# mosaico-dock-schematic.net
KiCad netlist of a schematic drawn in EasyEDA
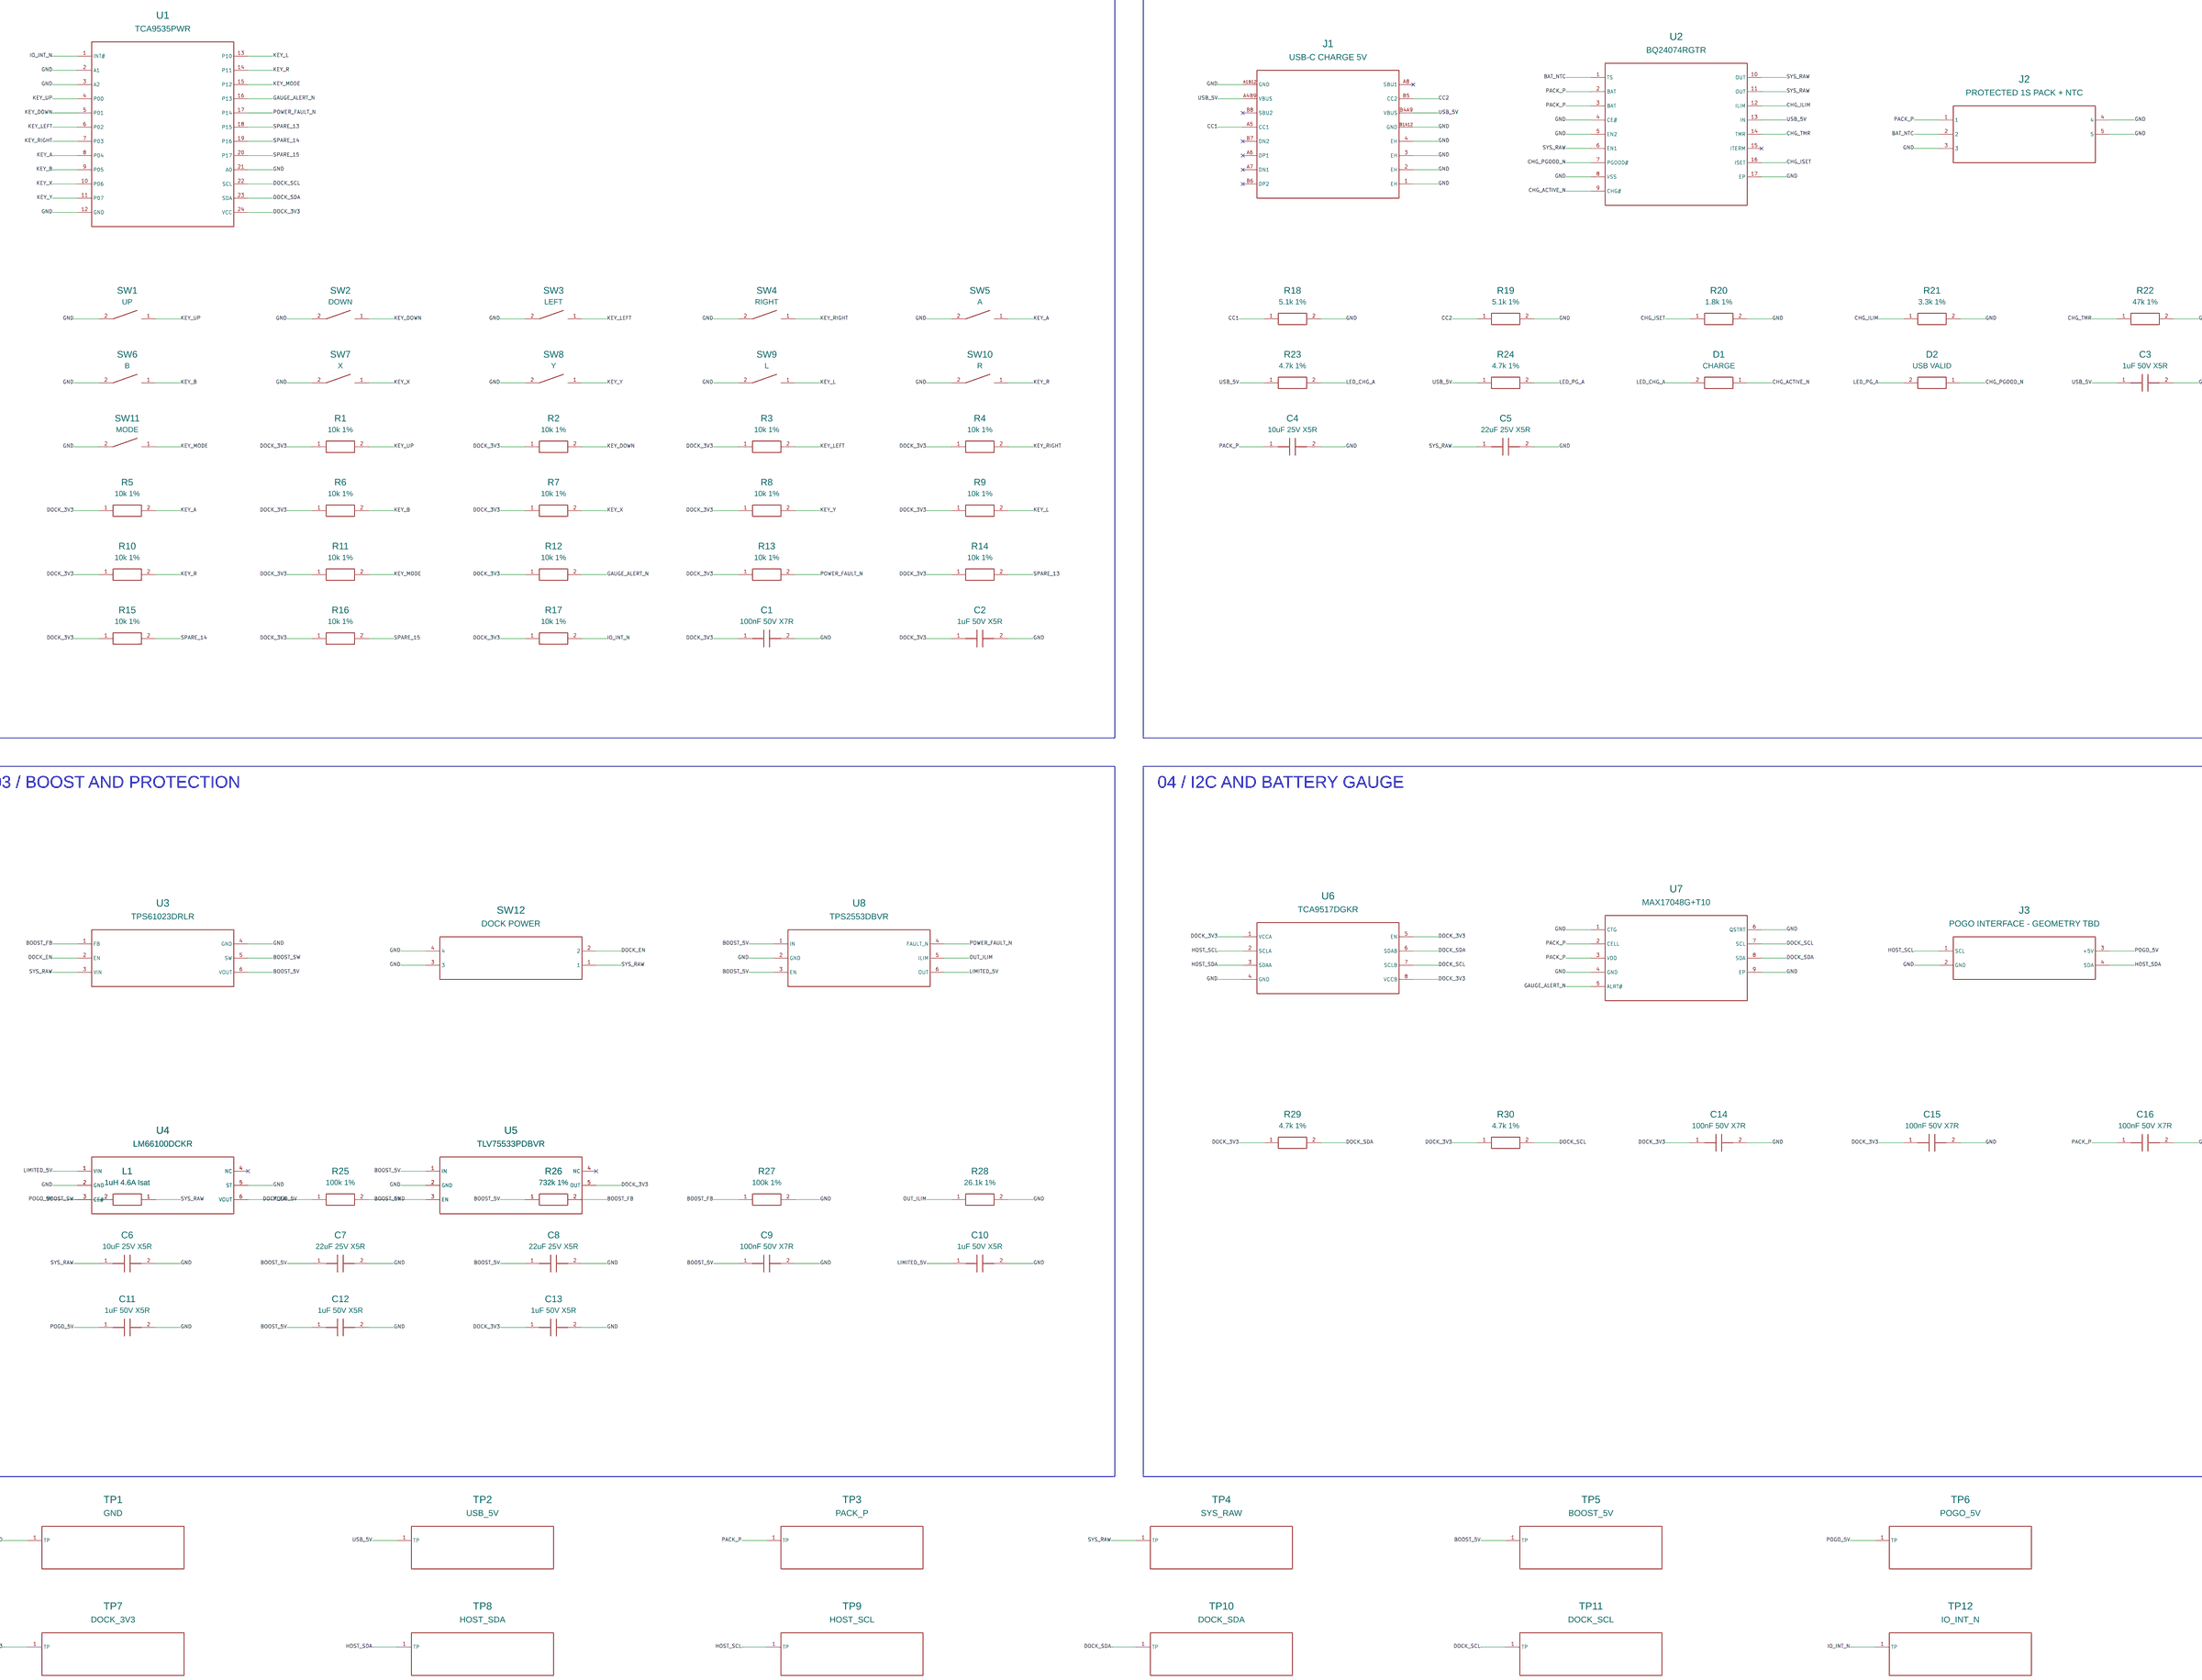
[diagram p0: schematic sheet]

(export (version "E")
  (design (tool "Eeschema 10.0.6"))
  (components
    (comp (ref "C1")
      (value "100nF 50V X7R")
      (fields
        (field (name "Manufacturer Part") "CL10B104KB8NNNC")
        (field (name "Manufacturer") "SAMSUNG(三星)")
      )
      (libsource (lib "") (part "100nF 50V X7R"))
    )
    (comp (ref "C2")
      (value "1uF 50V X5R")
      (fields
        (field (name "Manufacturer Part") "CL10A105KB8NNNC")
        (field (name "Manufacturer") "SAMSUNG(三星)")
      )
      (libsource (lib "") (part "1uF 50V X5R"))
    )
    (comp (ref "C3")
      (value "1uF 50V X5R")
      (fields
        (field (name "Manufacturer Part") "CL10A105KB8NNNC")
        (field (name "Manufacturer") "SAMSUNG(三星)")
      )
      (libsource (lib "") (part "1uF 50V X5R"))
    )
    (comp (ref "C4")
      (value "10uF 25V X5R")
      (fields
        (field (name "Manufacturer Part") "CL10A106MA8NRNC")
        (field (name "Manufacturer") "SAMSUNG(三星)")
      )
      (libsource (lib "") (part "10uF 25V X5R"))
    )
    (comp (ref "C5")
      (value "22uF 25V X5R")
      (fields
        (field (name "Manufacturer Part") "CL21A226MAQNNNE")
        (field (name "Manufacturer") "SAMSUNG(三星)")
      )
      (libsource (lib "") (part "22uF 25V X5R"))
    )
    (comp (ref "C6")
      (value "10uF 25V X5R")
      (fields
        (field (name "Manufacturer Part") "CL10A106MA8NRNC")
        (field (name "Manufacturer") "SAMSUNG(三星)")
      )
      (libsource (lib "") (part "10uF 25V X5R"))
    )
    (comp (ref "C7")
      (value "22uF 25V X5R")
      (fields
        (field (name "Manufacturer Part") "CL21A226MAQNNNE")
        (field (name "Manufacturer") "SAMSUNG(三星)")
      )
      (libsource (lib "") (part "22uF 25V X5R"))
    )
    (comp (ref "C8")
      (value "22uF 25V X5R")
      (fields
        (field (name "Manufacturer Part") "CL21A226MAQNNNE")
        (field (name "Manufacturer") "SAMSUNG(三星)")
      )
      (libsource (lib "") (part "22uF 25V X5R"))
    )
    (comp (ref "C9")
      (value "100nF 50V X7R")
      (fields
        (field (name "Manufacturer Part") "CL10B104KB8NNNC")
        (field (name "Manufacturer") "SAMSUNG(三星)")
      )
      (libsource (lib "") (part "100nF 50V X7R"))
    )
    (comp (ref "C10")
      (value "1uF 50V X5R")
      (fields
        (field (name "Manufacturer Part") "CL10A105KB8NNNC")
        (field (name "Manufacturer") "SAMSUNG(三星)")
      )
      (libsource (lib "") (part "1uF 50V X5R"))
    )
    (comp (ref "C11")
      (value "1uF 50V X5R")
      (fields
        (field (name "Manufacturer Part") "CL10A105KB8NNNC")
        (field (name "Manufacturer") "SAMSUNG(三星)")
      )
      (libsource (lib "") (part "1uF 50V X5R"))
    )
    (comp (ref "C12")
      (value "1uF 50V X5R")
      (fields
        (field (name "Manufacturer Part") "CL10A105KB8NNNC")
        (field (name "Manufacturer") "SAMSUNG(三星)")
      )
      (libsource (lib "") (part "1uF 50V X5R"))
    )
    (comp (ref "C13")
      (value "1uF 50V X5R")
      (fields
        (field (name "Manufacturer Part") "CL10A105KB8NNNC")
        (field (name "Manufacturer") "SAMSUNG(三星)")
      )
      (libsource (lib "") (part "1uF 50V X5R"))
    )
    (comp (ref "C14")
      (value "100nF 50V X7R")
      (fields
        (field (name "Manufacturer Part") "CL10B104KB8NNNC")
        (field (name "Manufacturer") "SAMSUNG(三星)")
      )
      (libsource (lib "") (part "100nF 50V X7R"))
    )
    (comp (ref "C15")
      (value "100nF 50V X7R")
      (fields
        (field (name "Manufacturer Part") "CL10B104KB8NNNC")
        (field (name "Manufacturer") "SAMSUNG(三星)")
      )
      (libsource (lib "") (part "100nF 50V X7R"))
    )
    (comp (ref "C16")
      (value "100nF 50V X7R")
      (fields
        (field (name "Manufacturer Part") "CL10B104KB8NNNC")
        (field (name "Manufacturer") "SAMSUNG(三星)")
      )
      (libsource (lib "") (part "100nF 50V X7R"))
    )
    (comp (ref "D1")
      (value "CHARGE")
      (fields (field (name "Manufacturer Part") "KT-0805黄灯") (field (name "Manufacturer") "KENTO"))
      (libsource (lib "") (part "CHARGE"))
    )
    (comp (ref "D2")
      (value "USB VALID")
      (fields (field (name "Manufacturer Part") "KT-0805黄灯") (field (name "Manufacturer") "KENTO"))
      (libsource (lib "") (part "USB VALID"))
    )
    (comp (ref "J1")
      (value "USB-C CHARGE 5V")
      (fields (field (name "Manufacturer Part") "TYPE-C-31-M-12") (field (name "Manufacturer") "韩国韩荣"))
      (libsource (lib "") (part "USB-C CHARGE 5V"))
    )
    (comp (ref "J2")
      (value "PROTECTED 1S PACK + NTC")
      (fields (field (name "Manufacturer Part") "B3B-PH-SM4-TB(LF)(SN)") (field (name "Manufacturer") "JST"))
      (libsource (lib "") (part "PROTECTED 1S PACK + NTC"))
    )
    (comp (ref "J3")
      (value "POGO INTERFACE - GEOMETRY TBD")
      (libsource (lib "") (part "POGO INTERFACE - GEOMETRY TBD"))
    )
    (comp (ref "L1")
      (value "1uH 4.6A Isat")
      (fields
        (field (name "Manufacturer Part") "FTC201610S1R0MBCA")
        (field (name "Manufacturer") "cjiang(长江微电)")
      )
      (libsource (lib "") (part "1uH 4.6A Isat"))
    )
    (comp (ref "R1")
      (value "10k 1%")
      (fields
        (field (name "Manufacturer Part") "0603WAF1002T5E")
        (field (name "Manufacturer") "UNI-ROYAL(厚声)")
      )
      (libsource (lib "") (part "10k 1%"))
    )
    (comp (ref "R2")
      (value "10k 1%")
      (fields
        (field (name "Manufacturer Part") "0603WAF1002T5E")
        (field (name "Manufacturer") "UNI-ROYAL(厚声)")
      )
      (libsource (lib "") (part "10k 1%"))
    )
    (comp (ref "R3")
      (value "10k 1%")
      (fields
        (field (name "Manufacturer Part") "0603WAF1002T5E")
        (field (name "Manufacturer") "UNI-ROYAL(厚声)")
      )
      (libsource (lib "") (part "10k 1%"))
    )
    (comp (ref "R4")
      (value "10k 1%")
      (fields
        (field (name "Manufacturer Part") "0603WAF1002T5E")
        (field (name "Manufacturer") "UNI-ROYAL(厚声)")
      )
      (libsource (lib "") (part "10k 1%"))
    )
    (comp (ref "R5")
      (value "10k 1%")
      (fields
        (field (name "Manufacturer Part") "0603WAF1002T5E")
        (field (name "Manufacturer") "UNI-ROYAL(厚声)")
      )
      (libsource (lib "") (part "10k 1%"))
    )
    (comp (ref "R6")
      (value "10k 1%")
      (fields
        (field (name "Manufacturer Part") "0603WAF1002T5E")
        (field (name "Manufacturer") "UNI-ROYAL(厚声)")
      )
      (libsource (lib "") (part "10k 1%"))
    )
    (comp (ref "R7")
      (value "10k 1%")
      (fields
        (field (name "Manufacturer Part") "0603WAF1002T5E")
        (field (name "Manufacturer") "UNI-ROYAL(厚声)")
      )
      (libsource (lib "") (part "10k 1%"))
    )
    (comp (ref "R8")
      (value "10k 1%")
      (fields
        (field (name "Manufacturer Part") "0603WAF1002T5E")
        (field (name "Manufacturer") "UNI-ROYAL(厚声)")
      )
      (libsource (lib "") (part "10k 1%"))
    )
    (comp (ref "R9")
      (value "10k 1%")
      (fields
        (field (name "Manufacturer Part") "0603WAF1002T5E")
        (field (name "Manufacturer") "UNI-ROYAL(厚声)")
      )
      (libsource (lib "") (part "10k 1%"))
    )
    (comp (ref "R10")
      (value "10k 1%")
      (fields
        (field (name "Manufacturer Part") "0603WAF1002T5E")
        (field (name "Manufacturer") "UNI-ROYAL(厚声)")
      )
      (libsource (lib "") (part "10k 1%"))
    )
    (comp (ref "R11")
      (value "10k 1%")
      (fields
        (field (name "Manufacturer Part") "0603WAF1002T5E")
        (field (name "Manufacturer") "UNI-ROYAL(厚声)")
      )
      (libsource (lib "") (part "10k 1%"))
    )
    (comp (ref "R12")
      (value "10k 1%")
      (fields
        (field (name "Manufacturer Part") "0603WAF1002T5E")
        (field (name "Manufacturer") "UNI-ROYAL(厚声)")
      )
      (libsource (lib "") (part "10k 1%"))
    )
    (comp (ref "R13")
      (value "10k 1%")
      (fields
        (field (name "Manufacturer Part") "0603WAF1002T5E")
        (field (name "Manufacturer") "UNI-ROYAL(厚声)")
      )
      (libsource (lib "") (part "10k 1%"))
    )
    (comp (ref "R14")
      (value "10k 1%")
      (fields
        (field (name "Manufacturer Part") "0603WAF1002T5E")
        (field (name "Manufacturer") "UNI-ROYAL(厚声)")
      )
      (libsource (lib "") (part "10k 1%"))
    )
    (comp (ref "R15")
      (value "10k 1%")
      (fields
        (field (name "Manufacturer Part") "0603WAF1002T5E")
        (field (name "Manufacturer") "UNI-ROYAL(厚声)")
      )
      (libsource (lib "") (part "10k 1%"))
    )
    (comp (ref "R16")
      (value "10k 1%")
      (fields
        (field (name "Manufacturer Part") "0603WAF1002T5E")
        (field (name "Manufacturer") "UNI-ROYAL(厚声)")
      )
      (libsource (lib "") (part "10k 1%"))
    )
    (comp (ref "R17")
      (value "10k 1%")
      (fields
        (field (name "Manufacturer Part") "0603WAF1002T5E")
        (field (name "Manufacturer") "UNI-ROYAL(厚声)")
      )
      (libsource (lib "") (part "10k 1%"))
    )
    (comp (ref "R18")
      (value "5.1k 1%")
      (fields
        (field (name "Manufacturer Part") "0603WAF5101T5E")
        (field (name "Manufacturer") "UNI-ROYAL(厚声)")
      )
      (libsource (lib "") (part "5.1k 1%"))
    )
    (comp (ref "R19")
      (value "5.1k 1%")
      (fields
        (field (name "Manufacturer Part") "0603WAF5101T5E")
        (field (name "Manufacturer") "UNI-ROYAL(厚声)")
      )
      (libsource (lib "") (part "5.1k 1%"))
    )
    (comp (ref "R20")
      (value "1.8k 1%")
      (fields
        (field (name "Manufacturer Part") "0603WAF1801T5E")
        (field (name "Manufacturer") "UNI-ROYAL(厚声)")
      )
      (libsource (lib "") (part "1.8k 1%"))
    )
    (comp (ref "R21")
      (value "3.3k 1%")
      (fields
        (field (name "Manufacturer Part") "0603WAF3301T5E")
        (field (name "Manufacturer") "UNI-ROYAL(厚声)")
      )
      (libsource (lib "") (part "3.3k 1%"))
    )
    (comp (ref "R22")
      (value "47k 1%")
      (fields
        (field (name "Manufacturer Part") "0603WAF4702T5E")
        (field (name "Manufacturer") "UNI-ROYAL(厚声)")
      )
      (libsource (lib "") (part "47k 1%"))
    )
    (comp (ref "R23")
      (value "4.7k 1%")
      (fields
        (field (name "Manufacturer Part") "0603WAF4701T5E")
        (field (name "Manufacturer") "UNI-ROYAL(厚声)")
      )
      (libsource (lib "") (part "4.7k 1%"))
    )
    (comp (ref "R24")
      (value "4.7k 1%")
      (fields
        (field (name "Manufacturer Part") "0603WAF4701T5E")
        (field (name "Manufacturer") "UNI-ROYAL(厚声)")
      )
      (libsource (lib "") (part "4.7k 1%"))
    )
    (comp (ref "R25")
      (value "100k 1%")
      (fields
        (field (name "Manufacturer Part") "0603WAF1003T5E")
        (field (name "Manufacturer") "UNI-ROYAL(厚声)")
      )
      (libsource (lib "") (part "100k 1%"))
    )
    (comp (ref "R26") (value "732k 1%") (libsource (lib "") (part "732k 1%")))
    (comp (ref "R27")
      (value "100k 1%")
      (fields
        (field (name "Manufacturer Part") "0603WAF1003T5E")
        (field (name "Manufacturer") "UNI-ROYAL(厚声)")
      )
      (libsource (lib "") (part "100k 1%"))
    )
    (comp (ref "R28") (value "26.1k 1%") (libsource (lib "") (part "26.1k 1%")))
    (comp (ref "R29")
      (value "4.7k 1%")
      (fields
        (field (name "Manufacturer Part") "0603WAF4701T5E")
        (field (name "Manufacturer") "UNI-ROYAL(厚声)")
      )
      (libsource (lib "") (part "4.7k 1%"))
    )
    (comp (ref "R30")
      (value "4.7k 1%")
      (fields
        (field (name "Manufacturer Part") "0603WAF4701T5E")
        (field (name "Manufacturer") "UNI-ROYAL(厚声)")
      )
      (libsource (lib "") (part "4.7k 1%"))
    )
    (comp (ref "SW1")
      (value "UP")
      (fields (field (name "Manufacturer Part") "TS-1088-AR02016") (field (name "Manufacturer") "XUNPU(讯普)"))
      (libsource (lib "") (part "UP"))
    )
    (comp (ref "SW2")
      (value "DOWN")
      (fields (field (name "Manufacturer Part") "TS-1088-AR02016") (field (name "Manufacturer") "XUNPU(讯普)"))
      (libsource (lib "") (part "DOWN"))
    )
    (comp (ref "SW3")
      (value "LEFT")
      (fields (field (name "Manufacturer Part") "TS-1088-AR02016") (field (name "Manufacturer") "XUNPU(讯普)"))
      (libsource (lib "") (part "LEFT"))
    )
    (comp (ref "SW4")
      (value "RIGHT")
      (fields (field (name "Manufacturer Part") "TS-1088-AR02016") (field (name "Manufacturer") "XUNPU(讯普)"))
      (libsource (lib "") (part "RIGHT"))
    )
    (comp (ref "SW5")
      (value "A")
      (fields (field (name "Manufacturer Part") "TS-1088-AR02016") (field (name "Manufacturer") "XUNPU(讯普)"))
      (libsource (lib "") (part "A"))
    )
    (comp (ref "SW6")
      (value "B")
      (fields (field (name "Manufacturer Part") "TS-1088-AR02016") (field (name "Manufacturer") "XUNPU(讯普)"))
      (libsource (lib "") (part "B"))
    )
    (comp (ref "SW7")
      (value "X")
      (fields (field (name "Manufacturer Part") "TS-1088-AR02016") (field (name "Manufacturer") "XUNPU(讯普)"))
      (libsource (lib "") (part "X"))
    )
    (comp (ref "SW8")
      (value "Y")
      (fields (field (name "Manufacturer Part") "TS-1088-AR02016") (field (name "Manufacturer") "XUNPU(讯普)"))
      (libsource (lib "") (part "Y"))
    )
    (comp (ref "SW9")
      (value "L")
      (fields (field (name "Manufacturer Part") "TS-1088-AR02016") (field (name "Manufacturer") "XUNPU(讯普)"))
      (libsource (lib "") (part "L"))
    )
    (comp (ref "SW10")
      (value "R")
      (fields (field (name "Manufacturer Part") "TS-1088-AR02016") (field (name "Manufacturer") "XUNPU(讯普)"))
      (libsource (lib "") (part "R"))
    )
    (comp (ref "SW11")
      (value "MODE")
      (fields (field (name "Manufacturer Part") "TS-1088-AR02016") (field (name "Manufacturer") "XUNPU(讯普)"))
      (libsource (lib "") (part "MODE"))
    )
    (comp (ref "SW12")
      (value "DOCK POWER")
      (fields (field (name "Manufacturer Part") "MSK12C02") (field (name "Manufacturer") "SHOU HAN(首韩)"))
      (libsource (lib "") (part "DOCK POWER"))
    )
    (comp (ref "TP1") (value "GND") (libsource (lib "") (part "GND")))
    (comp (ref "TP2") (value "USB_5V") (libsource (lib "") (part "USB_5V")))
    (comp (ref "TP3") (value "PACK_P") (libsource (lib "") (part "PACK_P")))
    (comp (ref "TP4") (value "SYS_RAW") (libsource (lib "") (part "SYS_RAW")))
    (comp (ref "TP5") (value "BOOST_5V") (libsource (lib "") (part "BOOST_5V")))
    (comp (ref "TP6") (value "POGO_5V") (libsource (lib "") (part "POGO_5V")))
    (comp (ref "TP7") (value "DOCK_3V3") (libsource (lib "") (part "DOCK_3V3")))
    (comp (ref "TP8") (value "HOST_SDA") (libsource (lib "") (part "HOST_SDA")))
    (comp (ref "TP9") (value "HOST_SCL") (libsource (lib "") (part "HOST_SCL")))
    (comp (ref "TP10") (value "DOCK_SDA") (libsource (lib "") (part "DOCK_SDA")))
    (comp (ref "TP11") (value "DOCK_SCL") (libsource (lib "") (part "DOCK_SCL")))
    (comp (ref "TP12") (value "IO_INT_N") (libsource (lib "") (part "IO_INT_N")))
    (comp (ref "U1")
      (value "TCA9535PWR")
      (fields (field (name "Manufacturer") "TI(德州仪器)"))
      (libsource (lib "") (part "TCA9535PWR"))
    )
    (comp (ref "U2")
      (value "BQ24074RGTR")
      (fields (field (name "Manufacturer") "TI(德州仪器)"))
      (libsource (lib "") (part "BQ24074RGTR"))
    )
    (comp (ref "U3")
      (value "TPS61023DRLR")
      (fields (field (name "Manufacturer") "TI(德州仪器)"))
      (libsource (lib "") (part "TPS61023DRLR"))
    )
    (comp (ref "U4")
      (value "LM66100DCKR")
      (fields (field (name "Manufacturer") "TI(德州仪器)"))
      (libsource (lib "") (part "LM66100DCKR"))
    )
    (comp (ref "U5")
      (value "TLV75533PDBVR")
      (fields (field (name "Manufacturer") "TI(德州仪器)"))
      (libsource (lib "") (part "TLV75533PDBVR"))
    )
    (comp (ref "U6")
      (value "TCA9517DGKR")
      (fields (field (name "Manufacturer") "TI(德州仪器)"))
      (libsource (lib "") (part "TCA9517DGKR"))
    )
    (comp (ref "U7")
      (value "MAX17048G+T10")
      (fields (field (name "Manufacturer") "ADI(亚德诺)/MAXIM(美信)"))
      (libsource (lib "") (part "MAX17048G+T10"))
    )
    (comp (ref "U8")
      (value "TPS2553DBVR")
      (fields (field (name "Manufacturer") "TI(德州仪器)"))
      (libsource (lib "") (part "TPS2553DBVR"))
    )
  )
  (nets
    (net (code "1") (name "/BAT_NTC") (class "Default")
      (node (ref "J2") (pin "2") (pinfunction "2_2") (pintype "unspecified"))
      (node (ref "U2") (pin "1") (pinfunction "TS_1") (pintype "unspecified"))
    )
    (net (code "2") (name "/BOOST_5V") (class "Default")
      (node (ref "C12") (pin "1") (pintype "unspecified"))
      (node (ref "C7") (pin "1") (pintype "unspecified"))
      (node (ref "C8") (pin "1") (pintype "unspecified"))
      (node (ref "C9") (pin "1") (pintype "unspecified"))
      (node (ref "R26") (pin "1") (pintype "unspecified"))
      (node (ref "TP5") (pin "1") (pinfunction "TP_1") (pintype "unspecified"))
      (node (ref "U3") (pin "6") (pinfunction "VOUT_6") (pintype "unspecified"))
      (node (ref "U5") (pin "1") (pinfunction "IN_1") (pintype "unspecified"))
      (node (ref "U5") (pin "3") (pinfunction "EN_3") (pintype "unspecified"))
      (node (ref "U8") (pin "1") (pinfunction "IN_1") (pintype "unspecified"))
      (node (ref "U8") (pin "3") (pinfunction "EN_3") (pintype "unspecified"))
    )
    (net (code "3") (name "/BOOST_FB") (class "Default")
      (node (ref "R26") (pin "2") (pintype "unspecified"))
      (node (ref "R27") (pin "1") (pintype "unspecified"))
      (node (ref "U3") (pin "1") (pinfunction "FB_1") (pintype "unspecified"))
    )
    (net (code "4") (name "/BOOST_SW") (class "Default")
      (node (ref "C11") (pin "1") (pintype "unspecified"))
      (node (ref "J3") (pin "3") (pinfunction "+5V_3") (pintype "unspecified"))
      (node (ref "L1") (pin "2") (pintype "unspecified"))
      (node (ref "TP6") (pin "1") (pinfunction "TP_1") (pintype "unspecified"))
      (node (ref "U3") (pin "5") (pinfunction "SW_5") (pintype "unspecified"))
      (node (ref "U4") (pin "3") (pinfunction "CE#_3") (pintype "unspecified"))
      (node (ref "U4") (pin "6") (pinfunction "VOUT_6") (pintype "unspecified"))
    )
    (net (code "5") (name "/CC1") (class "Default")
      (node (ref "J1") (pin "A5") (pinfunction "CC1_A5") (pintype "unspecified"))
      (node (ref "R18") (pin "1") (pintype "unspecified"))
    )
    (net (code "6") (name "/CC2") (class "Default")
      (node (ref "J1") (pin "B5") (pinfunction "CC2_B5") (pintype "unspecified"))
      (node (ref "R19") (pin "1") (pintype "unspecified"))
    )
    (net (code "7") (name "/CHG_ACTIVE_N") (class "Default")
      (node (ref "D1") (pin "1") (pintype "unspecified"))
      (node (ref "U2") (pin "9") (pinfunction "CHG#_9") (pintype "unspecified"))
    )
    (net (code "8") (name "/CHG_ILIM") (class "Default")
      (node (ref "R21") (pin "1") (pintype "unspecified"))
      (node (ref "U2") (pin "12") (pinfunction "ILIM_12") (pintype "unspecified"))
    )
    (net (code "9") (name "/CHG_ISET") (class "Default")
      (node (ref "R20") (pin "1") (pintype "unspecified"))
      (node (ref "U2") (pin "16") (pinfunction "ISET_16") (pintype "unspecified"))
    )
    (net (code "10") (name "/CHG_PGOOD_N") (class "Default")
      (node (ref "D2") (pin "1") (pintype "unspecified"))
      (node (ref "U2") (pin "7") (pinfunction "PGOOD#_7") (pintype "unspecified"))
    )
    (net (code "11") (name "/CHG_TMR") (class "Default")
      (node (ref "R22") (pin "1") (pintype "unspecified"))
      (node (ref "U2") (pin "14") (pinfunction "TMR_14") (pintype "unspecified"))
    )
    (net (code "12") (name "/DOCK_3V3") (class "Default")
      (node (ref "C1") (pin "1") (pintype "unspecified"))
      (node (ref "C13") (pin "1") (pintype "unspecified"))
      (node (ref "C14") (pin "1") (pintype "unspecified"))
      (node (ref "C15") (pin "1") (pintype "unspecified"))
      (node (ref "C2") (pin "1") (pintype "unspecified"))
      (node (ref "R1") (pin "1") (pintype "unspecified"))
      (node (ref "R10") (pin "1") (pintype "unspecified"))
      (node (ref "R11") (pin "1") (pintype "unspecified"))
      (node (ref "R12") (pin "1") (pintype "unspecified"))
      (node (ref "R13") (pin "1") (pintype "unspecified"))
      (node (ref "R14") (pin "1") (pintype "unspecified"))
      (node (ref "R15") (pin "1") (pintype "unspecified"))
      (node (ref "R16") (pin "1") (pintype "unspecified"))
      (node (ref "R17") (pin "1") (pintype "unspecified"))
      (node (ref "R2") (pin "1") (pintype "unspecified"))
      (node (ref "R29") (pin "1") (pintype "unspecified"))
      (node (ref "R3") (pin "1") (pintype "unspecified"))
      (node (ref "R30") (pin "1") (pintype "unspecified"))
      (node (ref "R4") (pin "1") (pintype "unspecified"))
      (node (ref "R5") (pin "1") (pintype "unspecified"))
      (node (ref "R6") (pin "1") (pintype "unspecified"))
      (node (ref "R7") (pin "1") (pintype "unspecified"))
      (node (ref "R8") (pin "1") (pintype "unspecified"))
      (node (ref "R9") (pin "1") (pintype "unspecified"))
      (node (ref "TP7") (pin "1") (pinfunction "TP_1") (pintype "unspecified"))
      (node (ref "U1") (pin "24") (pinfunction "VCC_24") (pintype "unspecified"))
      (node (ref "U5") (pin "5") (pinfunction "OUT_5") (pintype "unspecified"))
      (node (ref "U6") (pin "1") (pinfunction "VCCA_1") (pintype "unspecified"))
      (node (ref "U6") (pin "5") (pinfunction "EN_5") (pintype "unspecified"))
      (node (ref "U6") (pin "8") (pinfunction "VCCB_8") (pintype "unspecified"))
    )
    (net (code "13") (name "/DOCK_EN") (class "Default")
      (node (ref "R25") (pin "1") (pintype "unspecified"))
      (node (ref "SW12") (pin "2") (pinfunction "2_2") (pintype "unspecified"))
      (node (ref "U3") (pin "2") (pinfunction "EN_2") (pintype "unspecified"))
    )
    (net (code "14") (name "/DOCK_SCL") (class "Default")
      (node (ref "R30") (pin "2") (pintype "unspecified"))
      (node (ref "TP11") (pin "1") (pinfunction "TP_1") (pintype "unspecified"))
      (node (ref "U1") (pin "22") (pinfunction "SCL_22") (pintype "unspecified"))
      (node (ref "U6") (pin "7") (pinfunction "SCLB_7") (pintype "unspecified"))
      (node (ref "U7") (pin "7") (pinfunction "SCL_7") (pintype "unspecified"))
    )
    (net (code "15") (name "/DOCK_SDA") (class "Default")
      (node (ref "R29") (pin "2") (pintype "unspecified"))
      (node (ref "TP10") (pin "1") (pinfunction "TP_1") (pintype "unspecified"))
      (node (ref "U1") (pin "23") (pinfunction "SDA_23") (pintype "unspecified"))
      (node (ref "U6") (pin "6") (pinfunction "SDAB_6") (pintype "unspecified"))
      (node (ref "U7") (pin "8") (pinfunction "SDA_8") (pintype "unspecified"))
    )
    (net (code "16") (name "/GAUGE_ALERT_N") (class "Default")
      (node (ref "R12") (pin "2") (pintype "unspecified"))
      (node (ref "U1") (pin "16") (pinfunction "P13_16") (pintype "unspecified"))
      (node (ref "U7") (pin "5") (pinfunction "ALRT#_5") (pintype "unspecified"))
    )
    (net (code "17") (name "/GND") (class "Default")
      (node (ref "C1") (pin "2") (pintype "unspecified"))
      (node (ref "C10") (pin "2") (pintype "unspecified"))
      (node (ref "C11") (pin "2") (pintype "unspecified"))
      (node (ref "C12") (pin "2") (pintype "unspecified"))
      (node (ref "C13") (pin "2") (pintype "unspecified"))
      (node (ref "C14") (pin "2") (pintype "unspecified"))
      (node (ref "C15") (pin "2") (pintype "unspecified"))
      (node (ref "C16") (pin "2") (pintype "unspecified"))
      (node (ref "C2") (pin "2") (pintype "unspecified"))
      (node (ref "C3") (pin "2") (pintype "unspecified"))
      (node (ref "C4") (pin "2") (pintype "unspecified"))
      (node (ref "C5") (pin "2") (pintype "unspecified"))
      (node (ref "C6") (pin "2") (pintype "unspecified"))
      (node (ref "C7") (pin "2") (pintype "unspecified"))
      (node (ref "C8") (pin "2") (pintype "unspecified"))
      (node (ref "C9") (pin "2") (pintype "unspecified"))
      (node (ref "J1") (pin "1") (pinfunction "EH_1") (pintype "unspecified"))
      (node (ref "J1") (pin "2") (pinfunction "EH_2") (pintype "unspecified"))
      (node (ref "J1") (pin "3") (pinfunction "EH_3") (pintype "unspecified"))
      (node (ref "J1") (pin "4") (pinfunction "EH_4") (pintype "unspecified"))
      (node (ref "J1") (pin "A1B12") (pinfunction "GND_A1B12") (pintype "unspecified"))
      (node (ref "J1") (pin "B1A12") (pinfunction "GND_B1A12") (pintype "unspecified"))
      (node (ref "J2") (pin "3") (pinfunction "3_3") (pintype "unspecified"))
      (node (ref "J2") (pin "4") (pinfunction "4_4") (pintype "unspecified"))
      (node (ref "J2") (pin "5") (pinfunction "5_5") (pintype "unspecified"))
      (node (ref "J3") (pin "2") (pinfunction "GND_2") (pintype "unspecified"))
      (node (ref "R18") (pin "2") (pintype "unspecified"))
      (node (ref "R19") (pin "2") (pintype "unspecified"))
      (node (ref "R20") (pin "2") (pintype "unspecified"))
      (node (ref "R21") (pin "2") (pintype "unspecified"))
      (node (ref "R22") (pin "2") (pintype "unspecified"))
      (node (ref "R25") (pin "2") (pintype "unspecified"))
      (node (ref "R27") (pin "2") (pintype "unspecified"))
      (node (ref "R28") (pin "2") (pintype "unspecified"))
      (node (ref "SW1") (pin "2") (pintype "unspecified"))
      (node (ref "SW10") (pin "2") (pintype "unspecified"))
      (node (ref "SW11") (pin "2") (pintype "unspecified"))
      (node (ref "SW12") (pin "3") (pinfunction "3_3") (pintype "unspecified"))
      (node (ref "SW12") (pin "4") (pinfunction "4_4") (pintype "unspecified"))
      (node (ref "SW2") (pin "2") (pintype "unspecified"))
      (node (ref "SW3") (pin "2") (pintype "unspecified"))
      (node (ref "SW4") (pin "2") (pintype "unspecified"))
      (node (ref "SW5") (pin "2") (pintype "unspecified"))
      (node (ref "SW6") (pin "2") (pintype "unspecified"))
      (node (ref "SW7") (pin "2") (pintype "unspecified"))
      (node (ref "SW8") (pin "2") (pintype "unspecified"))
      (node (ref "SW9") (pin "2") (pintype "unspecified"))
      (node (ref "TP1") (pin "1") (pinfunction "TP_1") (pintype "unspecified"))
      (node (ref "U1") (pin "12") (pinfunction "GND_12") (pintype "unspecified"))
      (node (ref "U1") (pin "2") (pinfunction "A1_2") (pintype "unspecified"))
      (node (ref "U1") (pin "21") (pinfunction "A0_21") (pintype "unspecified"))
      (node (ref "U1") (pin "3") (pinfunction "A2_3") (pintype "unspecified"))
      (node (ref "U2") (pin "17") (pinfunction "EP_17") (pintype "unspecified"))
      (node (ref "U2") (pin "4") (pinfunction "CE#_4") (pintype "unspecified"))
      (node (ref "U2") (pin "5") (pinfunction "EN2_5") (pintype "unspecified"))
      (node (ref "U2") (pin "8") (pinfunction "VSS_8") (pintype "unspecified"))
      (node (ref "U3") (pin "4") (pinfunction "GND_4") (pintype "unspecified"))
      (node (ref "U4") (pin "2") (pinfunction "GND_2") (pintype "unspecified"))
      (node (ref "U4") (pin "5") (pinfunction "ST_5") (pintype "unspecified"))
      (node (ref "U5") (pin "2") (pinfunction "GND_2") (pintype "unspecified"))
      (node (ref "U6") (pin "4") (pinfunction "GND_4") (pintype "unspecified"))
      (node (ref "U7") (pin "1") (pinfunction "CTG_1") (pintype "unspecified"))
      (node (ref "U7") (pin "4") (pinfunction "GND_4") (pintype "unspecified"))
      (node (ref "U7") (pin "6") (pinfunction "QSTRT_6") (pintype "unspecified"))
      (node (ref "U7") (pin "9") (pinfunction "EP_9") (pintype "unspecified"))
      (node (ref "U8") (pin "2") (pinfunction "GND_2") (pintype "unspecified"))
    )
    (net (code "18") (name "/HOST_SCL") (class "Default")
      (node (ref "J3") (pin "1") (pinfunction "SCL_1") (pintype "unspecified"))
      (node (ref "TP9") (pin "1") (pinfunction "TP_1") (pintype "unspecified"))
      (node (ref "U6") (pin "2") (pinfunction "SCLA_2") (pintype "unspecified"))
    )
    (net (code "19") (name "/HOST_SDA") (class "Default")
      (node (ref "J3") (pin "4") (pinfunction "SDA_4") (pintype "unspecified"))
      (node (ref "TP8") (pin "1") (pinfunction "TP_1") (pintype "unspecified"))
      (node (ref "U6") (pin "3") (pinfunction "SDAA_3") (pintype "unspecified"))
    )
    (net (code "20") (name "/IO_INT_N") (class "Default")
      (node (ref "R17") (pin "2") (pintype "unspecified"))
      (node (ref "TP12") (pin "1") (pinfunction "TP_1") (pintype "unspecified"))
      (node (ref "U1") (pin "1") (pinfunction "INT#_1") (pintype "unspecified"))
    )
    (net (code "21") (name "/KEY_A") (class "Default")
      (node (ref "R5") (pin "2") (pintype "unspecified"))
      (node (ref "SW5") (pin "1") (pintype "unspecified"))
      (node (ref "U1") (pin "8") (pinfunction "P04_8") (pintype "unspecified"))
    )
    (net (code "22") (name "/KEY_B") (class "Default")
      (node (ref "R6") (pin "2") (pintype "unspecified"))
      (node (ref "SW6") (pin "1") (pintype "unspecified"))
      (node (ref "U1") (pin "9") (pinfunction "P05_9") (pintype "unspecified"))
    )
    (net (code "23") (name "/KEY_DOWN") (class "Default")
      (node (ref "R2") (pin "2") (pintype "unspecified"))
      (node (ref "SW2") (pin "1") (pintype "unspecified"))
      (node (ref "U1") (pin "5") (pinfunction "P01_5") (pintype "unspecified"))
    )
    (net (code "24") (name "/KEY_L") (class "Default")
      (node (ref "R9") (pin "2") (pintype "unspecified"))
      (node (ref "SW9") (pin "1") (pintype "unspecified"))
      (node (ref "U1") (pin "13") (pinfunction "P10_13") (pintype "unspecified"))
    )
    (net (code "25") (name "/KEY_LEFT") (class "Default")
      (node (ref "R3") (pin "2") (pintype "unspecified"))
      (node (ref "SW3") (pin "1") (pintype "unspecified"))
      (node (ref "U1") (pin "6") (pinfunction "P02_6") (pintype "unspecified"))
    )
    (net (code "26") (name "/KEY_MODE") (class "Default")
      (node (ref "R11") (pin "2") (pintype "unspecified"))
      (node (ref "SW11") (pin "1") (pintype "unspecified"))
      (node (ref "U1") (pin "15") (pinfunction "P12_15") (pintype "unspecified"))
    )
    (net (code "27") (name "/KEY_R") (class "Default")
      (node (ref "R10") (pin "2") (pintype "unspecified"))
      (node (ref "SW10") (pin "1") (pintype "unspecified"))
      (node (ref "U1") (pin "14") (pinfunction "P11_14") (pintype "unspecified"))
    )
    (net (code "28") (name "/KEY_RIGHT") (class "Default")
      (node (ref "R4") (pin "2") (pintype "unspecified"))
      (node (ref "SW4") (pin "1") (pintype "unspecified"))
      (node (ref "U1") (pin "7") (pinfunction "P03_7") (pintype "unspecified"))
    )
    (net (code "29") (name "/KEY_UP") (class "Default")
      (node (ref "R1") (pin "2") (pintype "unspecified"))
      (node (ref "SW1") (pin "1") (pintype "unspecified"))
      (node (ref "U1") (pin "4") (pinfunction "P00_4") (pintype "unspecified"))
    )
    (net (code "30") (name "/KEY_X") (class "Default")
      (node (ref "R7") (pin "2") (pintype "unspecified"))
      (node (ref "SW7") (pin "1") (pintype "unspecified"))
      (node (ref "U1") (pin "10") (pinfunction "P06_10") (pintype "unspecified"))
    )
    (net (code "31") (name "/KEY_Y") (class "Default")
      (node (ref "R8") (pin "2") (pintype "unspecified"))
      (node (ref "SW8") (pin "1") (pintype "unspecified"))
      (node (ref "U1") (pin "11") (pinfunction "P07_11") (pintype "unspecified"))
    )
    (net (code "32") (name "/LED_CHG_A") (class "Default")
      (node (ref "D1") (pin "2") (pintype "unspecified"))
      (node (ref "R23") (pin "2") (pintype "unspecified"))
    )
    (net (code "33") (name "/LED_PG_A") (class "Default")
      (node (ref "D2") (pin "2") (pintype "unspecified"))
      (node (ref "R24") (pin "2") (pintype "unspecified"))
    )
    (net (code "34") (name "/LIMITED_5V") (class "Default")
      (node (ref "C10") (pin "1") (pintype "unspecified"))
      (node (ref "U4") (pin "1") (pinfunction "VIN_1") (pintype "unspecified"))
      (node (ref "U8") (pin "6") (pinfunction "OUT_6") (pintype "unspecified"))
    )
    (net (code "35") (name "/OUT_ILIM") (class "Default")
      (node (ref "R28") (pin "1") (pintype "unspecified"))
      (node (ref "U8") (pin "5") (pinfunction "ILIM_5") (pintype "unspecified"))
    )
    (net (code "36") (name "/PACK_P") (class "Default")
      (node (ref "C16") (pin "1") (pintype "unspecified"))
      (node (ref "C4") (pin "1") (pintype "unspecified"))
      (node (ref "J2") (pin "1") (pinfunction "1_1") (pintype "unspecified"))
      (node (ref "TP3") (pin "1") (pinfunction "TP_1") (pintype "unspecified"))
      (node (ref "U2") (pin "2") (pinfunction "BAT_2") (pintype "unspecified"))
      (node (ref "U2") (pin "3") (pinfunction "BAT_3") (pintype "unspecified"))
      (node (ref "U7") (pin "2") (pinfunction "CELL_2") (pintype "unspecified"))
      (node (ref "U7") (pin "3") (pinfunction "VDD_3") (pintype "unspecified"))
    )
    (net (code "37") (name "/POWER_FAULT_N") (class "Default")
      (node (ref "R13") (pin "2") (pintype "unspecified"))
      (node (ref "U1") (pin "17") (pinfunction "P14_17") (pintype "unspecified"))
      (node (ref "U8") (pin "4") (pinfunction "FAULT_N_4") (pintype "unspecified"))
    )
    (net (code "38") (name "/SPARE_13") (class "Default")
      (node (ref "R14") (pin "2") (pintype "unspecified"))
      (node (ref "U1") (pin "18") (pinfunction "P15_18") (pintype "unspecified"))
    )
    (net (code "39") (name "/SPARE_14") (class "Default")
      (node (ref "R15") (pin "2") (pintype "unspecified"))
      (node (ref "U1") (pin "19") (pinfunction "P16_19") (pintype "unspecified"))
    )
    (net (code "40") (name "/SPARE_15") (class "Default")
      (node (ref "R16") (pin "2") (pintype "unspecified"))
      (node (ref "U1") (pin "20") (pinfunction "P17_20") (pintype "unspecified"))
    )
    (net (code "41") (name "/SYS_RAW") (class "Default")
      (node (ref "C5") (pin "1") (pintype "unspecified"))
      (node (ref "C6") (pin "1") (pintype "unspecified"))
      (node (ref "L1") (pin "1") (pintype "unspecified"))
      (node (ref "SW12") (pin "1") (pinfunction "1_1") (pintype "unspecified"))
      (node (ref "TP4") (pin "1") (pinfunction "TP_1") (pintype "unspecified"))
      (node (ref "U2") (pin "10") (pinfunction "OUT_10") (pintype "unspecified"))
      (node (ref "U2") (pin "11") (pinfunction "OUT_11") (pintype "unspecified"))
      (node (ref "U2") (pin "6") (pinfunction "EN1_6") (pintype "unspecified"))
      (node (ref "U3") (pin "3") (pinfunction "VIN_3") (pintype "unspecified"))
    )
    (net (code "42") (name "/USB_5V") (class "Default")
      (node (ref "C3") (pin "1") (pintype "unspecified"))
      (node (ref "J1") (pin "A4B9") (pinfunction "VBUS_A4B9") (pintype "unspecified"))
      (node (ref "J1") (pin "B4A9") (pinfunction "VBUS_B4A9") (pintype "unspecified"))
      (node (ref "R23") (pin "1") (pintype "unspecified"))
      (node (ref "R24") (pin "1") (pintype "unspecified"))
      (node (ref "TP2") (pin "1") (pinfunction "TP_1") (pintype "unspecified"))
      (node (ref "U2") (pin "13") (pinfunction "IN_13") (pintype "unspecified"))
    )
    (net (code "43") (name "unconnected-(J1-DN1-PadA7)") (class "Default")
      (node (ref "J1") (pin "A7") (pinfunction "DN1_A7") (pintype "unspecified+no_connect"))
    )
    (net (code "44") (name "unconnected-(J1-DN2-PadB7)") (class "Default")
      (node (ref "J1") (pin "B7") (pinfunction "DN2_B7") (pintype "unspecified+no_connect"))
    )
    (net (code "45") (name "unconnected-(J1-DP1-PadA6)") (class "Default")
      (node (ref "J1") (pin "A6") (pinfunction "DP1_A6") (pintype "unspecified+no_connect"))
    )
    (net (code "46") (name "unconnected-(J1-DP2-PadB6)") (class "Default")
      (node (ref "J1") (pin "B6") (pinfunction "DP2_B6") (pintype "unspecified+no_connect"))
    )
    (net (code "47") (name "unconnected-(J1-SBU1-PadA8)") (class "Default")
      (node (ref "J1") (pin "A8") (pinfunction "SBU1_A8") (pintype "unspecified+no_connect"))
    )
    (net (code "48") (name "unconnected-(J1-SBU2-PadB8)") (class "Default")
      (node (ref "J1") (pin "B8") (pinfunction "SBU2_B8") (pintype "unspecified+no_connect"))
    )
    (net (code "49") (name "unconnected-(U2-ITERM-Pad15)") (class "Default")
      (node (ref "U2") (pin "15") (pinfunction "ITERM_15") (pintype "unspecified+no_connect"))
    )
    (net (code "50") (name "unconnected-(U4-NC-Pad4)") (class "Default")
      (node (ref "U4") (pin "4") (pinfunction "NC_4") (pintype "unspecified+no_connect"))
    )
    (net (code "51") (name "unconnected-(U5-NC-Pad4)") (class "Default")
      (node (ref "U5") (pin "4") (pinfunction "NC_4") (pintype "unspecified+no_connect"))
    )
  )
)
